# FLASHLIGHT_MAIN_SCH.net
KiCad netlist of a schematic drawn in Altium Designer
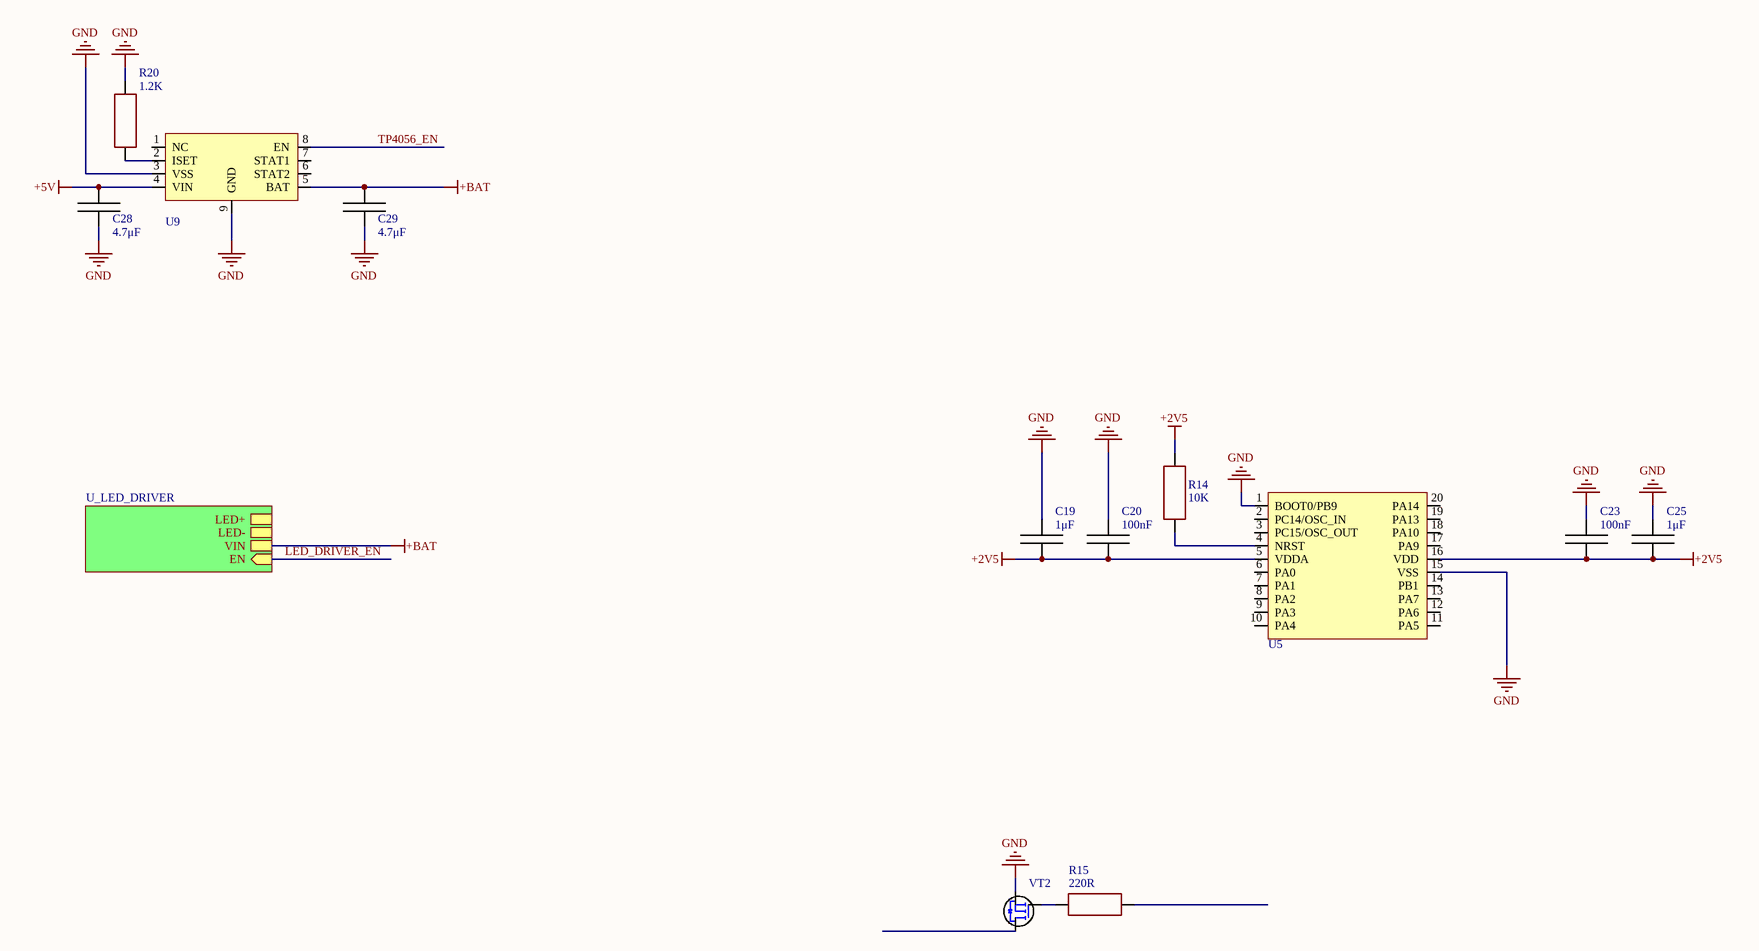
[diagram p0: FLASHLIGHT_MAIN_SCH.SchDoc]

(export (version "E")
  (design (tool "Eeschema 10.0.6"))
  (components
    (comp (ref "C19")
      (value "1μF")
      (footprint "CAP: 0402")
      (fields (field (name "VOLTAGE") "??V") (field (name "Comment") "Cap_0402"))
      (libsource (lib "capacitor") (part "Cap_0402"))
    )
    (comp (ref "C20")
      (value "100nF")
      (footprint "CAP: 0402")
      (fields (field (name "VOLTAGE") "??V") (field (name "Comment") "Cap_0402"))
      (libsource (lib "capacitor") (part "Cap_0402"))
    )
    (comp (ref "C23")
      (value "100nF")
      (footprint "CAP: 0402")
      (fields (field (name "VOLTAGE") "??V") (field (name "Comment") "Cap_0402"))
      (libsource (lib "capacitor") (part "Cap_0402"))
    )
    (comp (ref "C25")
      (value "1μF")
      (footprint "CAP: 0402")
      (fields (field (name "VOLTAGE") "??V") (field (name "Comment") "Cap_0402"))
      (libsource (lib "capacitor") (part "Cap_0402"))
    )
    (comp (ref "C28")
      (value "4.7μF")
      (footprint "CAP: 0402")
      (fields (field (name "VOLTAGE") "X5R 6.3В 20%") (field (name "Comment") "Cap_0402"))
      (libsource (lib "capacitor") (part "Cap_0402"))
    )
    (comp (ref "C29")
      (value "4.7μF")
      (footprint "CAP: 0402")
      (fields (field (name "VOLTAGE") "X5R 6.3В 20%") (field (name "Comment") "Cap_0402"))
      (libsource (lib "capacitor") (part "Cap_0402"))
    )
    (comp (ref "R14")
      (value "10K")
      (footprint "standard-case:RES: 0402")
      (fields (field (name "TOLERANCE") "±5%"))
      (libsource (lib "resistor") (part "Resistor_0402"))
    )
    (comp (ref "R15")
      (value "220R")
      (footprint "standard-case:RES: 0402")
      (fields (field (name "TOLERANCE") "±5%"))
      (libsource (lib "") (part "Resistor_0402_2"))
    )
    (comp (ref "R20")
      (value "1.2K")
      (footprint "RES: 0402")
      (fields (field (name "TOLERANCE") "±5%"))
      (libsource (lib "") (part "Resistor_0402_1"))
    )
    (comp (ref "U5")
      (value "STM32L011F4P6TR")
      (footprint "TSSOP-20")
      (fields (field (name "MANUFACTURER") "STMicroelectronics"))
      (libsource (lib "MY_INT_LIB") (part "STM32L011F4P6TR"))
    )
    (comp (ref "U9")
      (value "TP4056")
      (footprint "ESOP-8")
      (description "1s charge module")
      (fields (field (name "MANUFACTURER") "UMW"))
      (libsource (lib "MY_INT_LIB") (part "TP4056"))
    )
    (comp (ref "VT2")
      (value "IRLML6344")
      (footprint "SOT-23-3")
      (description "MOSFET N-CHANNEL 30V 5A")
      (fields (field (name "MANUFACTURER") "Fairchild"))
      (libsource (lib "MY_INT_LIB") (part "IRLML6344"))
    )
  )
  (nets
    (net (code "1") (name "+2V5") (class "Default")
      (node (ref "C19") (pin "1") (pinfunction "1_1") (pintype "passive"))
      (node (ref "C20") (pin "2") (pinfunction "2_2") (pintype "passive"))
      (node (ref "C23") (pin "2") (pinfunction "2_2") (pintype "passive"))
      (node (ref "C25") (pin "1") (pinfunction "1_1") (pintype "passive"))
      (node (ref "R14") (pin "1") (pinfunction "1_1") (pintype "passive"))
      (node (ref "U5") (pin "16") (pinfunction "VDD_16") (pintype "power_in"))
      (node (ref "U5") (pin "5") (pinfunction "VDDA_5") (pintype "power_in"))
    )
    (net (code "2") (name "+5V") (class "Default")
      (node (ref "C28") (pin "2") (pinfunction "2_2") (pintype "passive"))
      (node (ref "U9") (pin "4") (pinfunction "VIN_4") (pintype "passive"))
    )
    (net (code "3") (name "+BAT") (class "Default")
      (node (ref "C29") (pin "2") (pinfunction "2_2") (pintype "passive"))
      (node (ref "U9") (pin "5") (pinfunction "BAT_5") (pintype "passive"))
    )
    (net (code "7") (name "/TP4056_EN") (class "Default")
      (node (ref "U9") (pin "8") (pinfunction "EN_8") (pintype "passive"))
    )
    (net (code "8") (name "GND") (class "Default")
      (node (ref "C19") (pin "2") (pinfunction "2_2") (pintype "passive"))
      (node (ref "C20") (pin "1") (pinfunction "1_1") (pintype "passive"))
      (node (ref "C23") (pin "1") (pinfunction "1_1") (pintype "passive"))
      (node (ref "C25") (pin "2") (pinfunction "2_2") (pintype "passive"))
      (node (ref "C28") (pin "1") (pinfunction "1_1") (pintype "passive"))
      (node (ref "C29") (pin "1") (pinfunction "1_1") (pintype "passive"))
      (node (ref "R20") (pin "2") (pinfunction "2_2") (pintype "passive"))
      (node (ref "U5") (pin "1") (pinfunction "BOOT0/PB9_1") (pintype "passive"))
      (node (ref "U5") (pin "15") (pinfunction "VSS_15") (pintype "power_in"))
      (node (ref "U9") (pin "3") (pinfunction "VSS_3") (pintype "passive"))
      (node (ref "U9") (pin "9") (pinfunction "GND_9") (pintype "passive"))
      (node (ref "VT2") (pin "2") (pintype "power_in"))
    )
    (net (code "9") (name "Net-(R15-Pad1)") (class "Default")
      (node (ref "R15") (pin "1") (pinfunction "1_1") (pintype "passive"))
      (node (ref "VT2") (pin "1") (pintype "power_in"))
    )
    (net (code "10") (name "Net-(U5-NRST)") (class "Default")
      (node (ref "R14") (pin "2") (pinfunction "2_2") (pintype "passive"))
      (node (ref "U5") (pin "4") (pinfunction "NRST_4") (pintype "passive"))
    )
    (net (code "11") (name "Net-(U9-ISET)") (class "Default")
      (node (ref "R20") (pin "1") (pinfunction "1_1") (pintype "passive"))
      (node (ref "U9") (pin "2") (pinfunction "ISET_2") (pintype "passive"))
    )
    (net (code "12") (name "unconnected-(R15-Pad2)") (class "Default")
      (node (ref "R15") (pin "2") (pinfunction "2_2") (pintype "passive"))
    )
    (net (code "13") (name "unconnected-(U5-PA0-Pad6)") (class "Default")
      (node (ref "U5") (pin "6") (pinfunction "PA0_6") (pintype "passive"))
    )
    (net (code "14") (name "unconnected-(U5-PA1-Pad7)") (class "Default")
      (node (ref "U5") (pin "7") (pinfunction "PA1_7") (pintype "passive"))
    )
    (net (code "15") (name "unconnected-(U5-PA2-Pad8)") (class "Default")
      (node (ref "U5") (pin "8") (pinfunction "PA2_8") (pintype "passive"))
    )
    (net (code "16") (name "unconnected-(U5-PA3-Pad9)") (class "Default")
      (node (ref "U5") (pin "9") (pinfunction "PA3_9") (pintype "passive"))
    )
    (net (code "17") (name "unconnected-(U5-PA4-Pad10)") (class "Default")
      (node (ref "U5") (pin "10") (pinfunction "PA4_10") (pintype "passive"))
    )
    (net (code "18") (name "unconnected-(U5-PA5-Pad11)") (class "Default")
      (node (ref "U5") (pin "11") (pinfunction "PA5_11") (pintype "passive"))
    )
    (net (code "19") (name "unconnected-(U5-PA6-Pad12)") (class "Default")
      (node (ref "U5") (pin "12") (pinfunction "PA6_12") (pintype "passive"))
    )
    (net (code "20") (name "unconnected-(U5-PA7-Pad13)") (class "Default")
      (node (ref "U5") (pin "13") (pinfunction "PA7_13") (pintype "passive"))
    )
    (net (code "21") (name "unconnected-(U5-PA9-Pad17)") (class "Default")
      (node (ref "U5") (pin "17") (pinfunction "PA9_17") (pintype "passive"))
    )
    (net (code "22") (name "unconnected-(U5-PA10-Pad18)") (class "Default")
      (node (ref "U5") (pin "18") (pinfunction "PA10_18") (pintype "passive"))
    )
    (net (code "23") (name "unconnected-(U5-PA13-Pad19)") (class "Default")
      (node (ref "U5") (pin "19") (pinfunction "PA13_19") (pintype "passive"))
    )
    (net (code "24") (name "unconnected-(U5-PA14-Pad20)") (class "Default")
      (node (ref "U5") (pin "20") (pinfunction "PA14_20") (pintype "passive"))
    )
    (net (code "25") (name "unconnected-(U5-PB1-Pad14)") (class "Default")
      (node (ref "U5") (pin "14") (pinfunction "PB1_14") (pintype "passive"))
    )
    (net (code "26") (name "unconnected-(U5-PC14{slash}OSC_IN-Pad2)") (class "Default")
      (node (ref "U5") (pin "2") (pinfunction "PC14/OSC_IN_2") (pintype "passive"))
    )
    (net (code "27") (name "unconnected-(U5-PC15{slash}OSC_OUT-Pad3)") (class "Default")
      (node (ref "U5") (pin "3") (pinfunction "PC15/OSC_OUT_3") (pintype "passive"))
    )
    (net (code "28") (name "unconnected-(U9-NC-Pad1)") (class "Default")
      (node (ref "U9") (pin "1") (pinfunction "NC_1") (pintype "passive"))
    )
    (net (code "29") (name "unconnected-(U9-STAT1-Pad7)") (class "Default")
      (node (ref "U9") (pin "7") (pinfunction "STAT1_7") (pintype "passive"))
    )
    (net (code "30") (name "unconnected-(U9-STAT2-Pad6)") (class "Default")
      (node (ref "U9") (pin "6") (pinfunction "STAT2_6") (pintype "passive"))
    )
    (net (code "31") (name "unconnected-(VT2-Pad3)") (class "Default")
      (node (ref "VT2") (pin "3") (pintype "power_in"))
    )
  )
)
